# 468323_001_EEPROM.net
KiCad netlist of a schematic drawn in Altium Designer
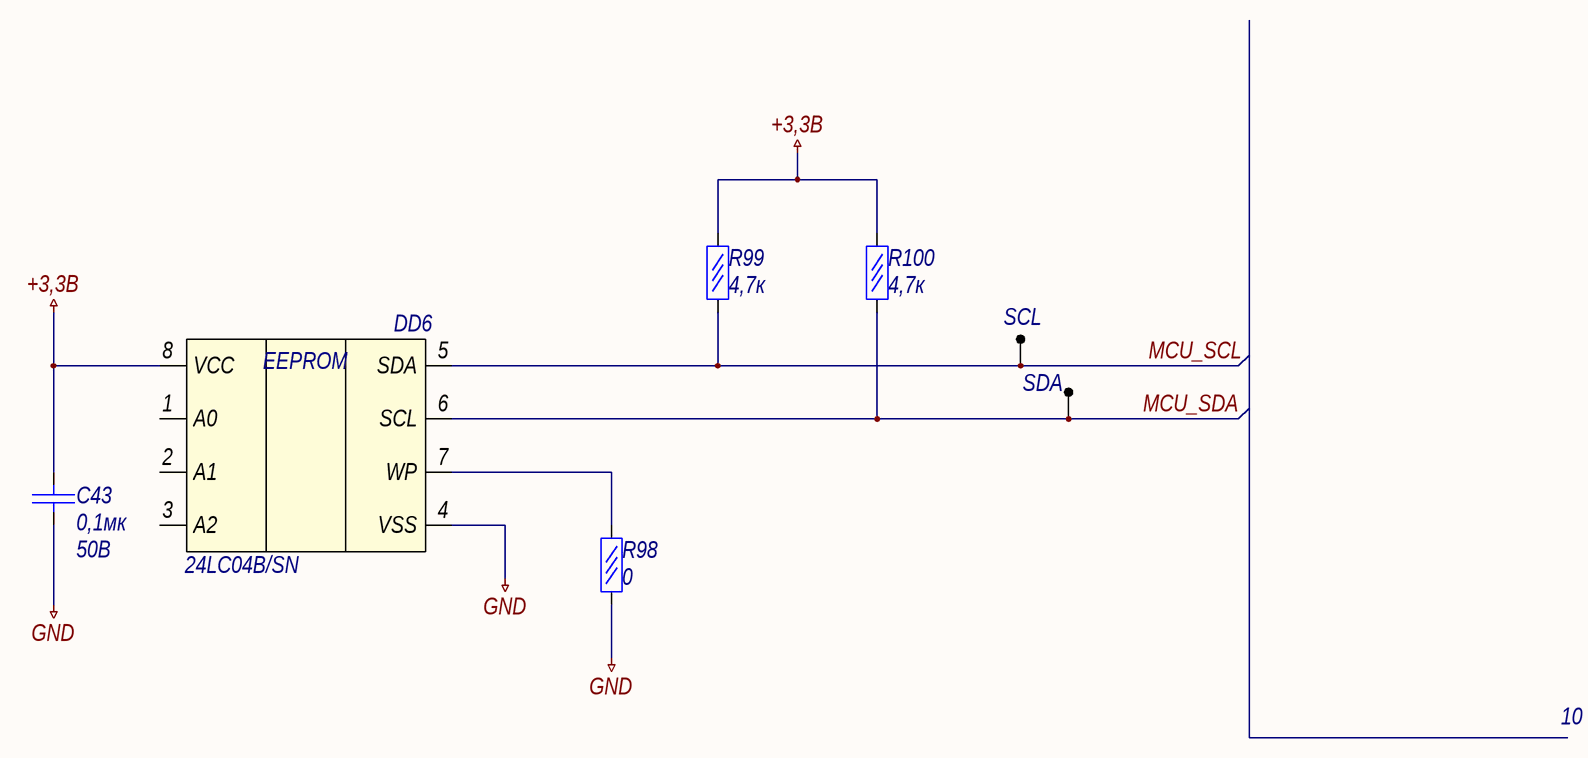
[diagram p0: РЕУН.468323.001_EEPROM.SchDoc]

(export (version "E")
  (design (tool "Eeschema 10.0.6"))
  (components
    (comp (ref "C43")
      (value "0,1мк")
      (footprint "C0805_AA")
      (description "Конденсатор кер.")
      (fields (field (name "VOLTAGE") "50В"))
      (libsource (lib "Library_Diana") (part "Конденсатор кер."))
    )
    (comp (ref "DD6")
      (value "24LC04B/SN")
      (description "4K I2C Serial EEPROM")
      (libsource (lib "Library_Diana") (part "24LC04B"))
    )
    (comp (ref "R98")
      (value "0")
      (footprint "R1206")
      (description "Резистор 0,05Вт")
      (libsource (lib "Library_Diana") (part "Резистор  0,05Вт"))
    )
    (comp (ref "R99")
      (value "4,7к")
      (footprint "R1206")
      (description "Резистор 0,05Вт")
      (libsource (lib "Library_Diana") (part "Резистор  0,05Вт"))
    )
    (comp (ref "R100")
      (value "4,7к")
      (footprint "R1206")
      (description "Резистор 0,05Вт")
      (libsource (lib "Library_Diana") (part "Резистор  0,05Вт"))
    )
    (comp (ref "SCL")
      (value "\"1\"")
      (footprint "0.5 x 1_round")
      (description "Test point")
      (libsource (lib "TarabusLib_KOR") (part "TestPoint"))
    )
    (comp (ref "SDA")
      (value "\"1\"")
      (footprint "0.5 x 1_round")
      (description "Test point")
      (libsource (lib "TarabusLib_KOR") (part "TestPoint"))
    )
  )
  (nets
    (net (code "1") (name "+3,3В") (class "Default")
      (node (ref "C43") (pin "2") (pinfunction "2_2") (pintype "passive"))
      (node (ref "DD6") (pin "8") (pinfunction "VCC_8") (pintype "power_in"))
      (node (ref "R100") (pin "2") (pinfunction "2_2") (pintype "passive"))
      (node (ref "R99") (pin "2") (pinfunction "2_2") (pintype "passive"))
    )
    (net (code "2") (name "/MCU_SCL") (class "Default")
      (node (ref "DD6") (pin "5") (pinfunction "SDA_5") (pintype "power_in"))
      (node (ref "R99") (pin "1") (pinfunction "1_1") (pintype "passive"))
      (node (ref "SCL") (pin "1") (pinfunction "1_1") (pintype "passive"))
    )
    (net (code "3") (name "/MCU_SDA") (class "Default")
      (node (ref "DD6") (pin "6") (pinfunction "SCL_6") (pintype "power_in"))
      (node (ref "R100") (pin "1") (pinfunction "1_1") (pintype "passive"))
      (node (ref "SDA") (pin "1") (pinfunction "1_1") (pintype "passive"))
    )
    (net (code "4") (name "GND") (class "Default")
      (node (ref "C43") (pin "1") (pinfunction "1_1") (pintype "passive"))
      (node (ref "DD6") (pin "4") (pinfunction "VSS_4") (pintype "power_in"))
      (node (ref "R98") (pin "1") (pinfunction "1_1") (pintype "passive"))
    )
    (net (code "5") (name "Net-(DD6-WP)") (class "Default")
      (node (ref "DD6") (pin "7") (pinfunction "WP_7") (pintype "power_in"))
      (node (ref "R98") (pin "2") (pinfunction "2_2") (pintype "passive"))
    )
    (net (code "6") (name "unconnected-(DD6-A0-Pad1)") (class "Default")
      (node (ref "DD6") (pin "1") (pinfunction "A0_1") (pintype "power_in"))
    )
    (net (code "7") (name "unconnected-(DD6-A1-Pad2)") (class "Default")
      (node (ref "DD6") (pin "2") (pinfunction "A1_2") (pintype "power_in"))
    )
    (net (code "8") (name "unconnected-(DD6-A2-Pad3)") (class "Default")
      (node (ref "DD6") (pin "3") (pinfunction "A2_3") (pintype "power_in"))
    )
  )
)
